# encoder-breakout-thin.net
KiCad netlist of a schematic drawn in EAGLE
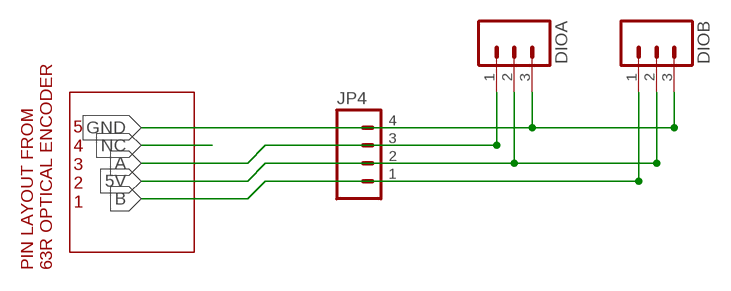
[diagram p0: schematic, sheet 1]

(export (version "E")
  (design (tool "Eeschema 10.0.6"))
  (components
    (comp (ref "DIOA")
      (value "M03LOCK")
      (footprint "eagle-import:1X03_LOCK")
      (libsource (lib "eagle-import") (part "M03LOCK"))
    )
    (comp (ref "DIOB")
      (value "M03LOCK")
      (footprint "eagle-import:1X03_LOCK")
      (libsource (lib "eagle-import") (part "M03LOCK"))
    )
    (comp (ref "JP4")
      (value "M04LOCK")
      (footprint "eagle-import:1X04_LOCK")
      (libsource (lib "eagle-import") (part "M04LOCK"))
    )
  )
  (nets
    (net (code "1") (name "5V") (class "Default")
      (node (ref "DIOA") (pin "2") (pinfunction "2_2") (pintype "passive"))
      (node (ref "DIOB") (pin "2") (pinfunction "2_2") (pintype "passive"))
      (node (ref "JP4") (pin "2") (pinfunction "2_2") (pintype "passive"))
    )
    (net (code "2") (name "A") (class "Default")
      (node (ref "DIOA") (pin "1") (pinfunction "1_1") (pintype "passive"))
      (node (ref "JP4") (pin "3") (pinfunction "3_3") (pintype "passive"))
    )
    (net (code "3") (name "B") (class "Default")
      (node (ref "DIOB") (pin "1") (pinfunction "1_1") (pintype "passive"))
      (node (ref "JP4") (pin "1") (pinfunction "1_1") (pintype "passive"))
    )
    (net (code "4") (name "GND") (class "Default")
      (node (ref "DIOA") (pin "3") (pinfunction "3_3") (pintype "passive"))
      (node (ref "DIOB") (pin "3") (pinfunction "3_3") (pintype "passive"))
      (node (ref "JP4") (pin "4") (pinfunction "4_4") (pintype "passive"))
    )
  )
)
